# pb-autoreverse.net
KiCad netlist of a schematic drawn in Altium Designer
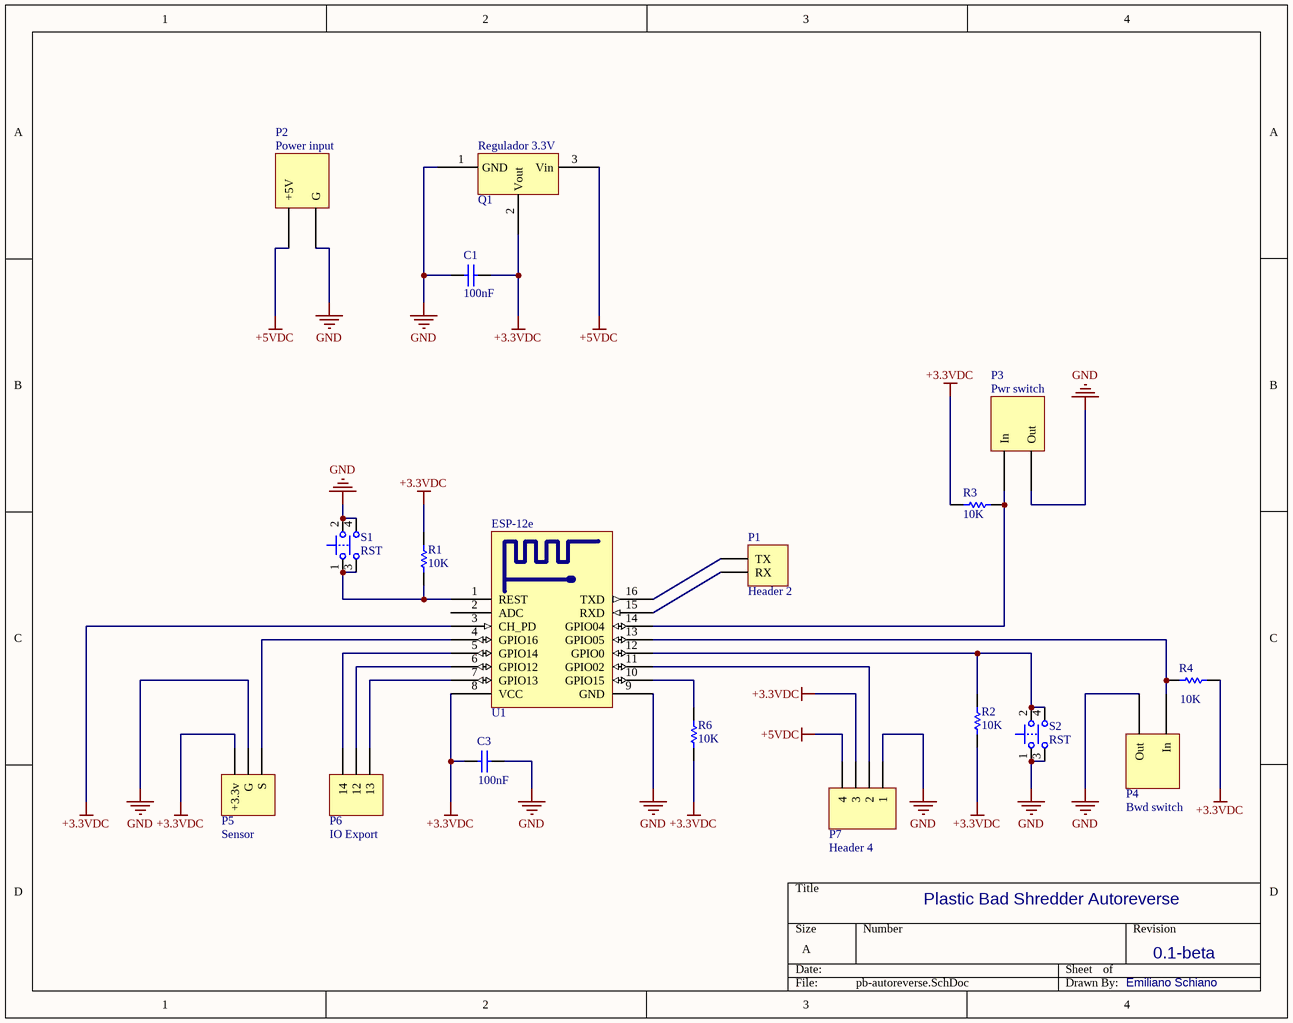
[diagram p0: pb-autoreverse.SchDoc]

(export (version "E")
  (design (tool "Eeschema 10.0.6"))
  (components
    (comp (ref "C1")
      (value "100nF")
      (footprint "RAD-0.1")
      (description "Capacitor")
      (fields (field (name "Comment") "100nf") (field (name "PUBLISHER") "Altium Limited"))
      (libsource (lib "Miscellaneous Devices") (part "Cap"))
    )
    (comp (ref "C3")
      (value "100nF")
      (footprint "RAD-0.1")
      (description "Capacitor")
      (fields (field (name "Comment") "100nf") (field (name "PUBLISHER") "Altium Limited"))
      (libsource (lib "Miscellaneous Devices") (part "Cap"))
    )
    (comp (ref "P1")
      (value "Header 2")
      (footprint "HDR1X2")
      (description "Header, 2-Pin")
      (fields (field (name "PUBLISHER") "Altium Limited"))
      (libsource (lib "Miscellaneous Connectors") (part "Header 2"))
    )
    (comp (ref "P2")
      (value "Power input")
      (footprint "ScrewTerminal-X2")
      (libsource (lib "") (part "ScrewTerminal_1"))
    )
    (comp (ref "P3")
      (value "Pwr switch")
      (footprint "ScrewTerminal-X2")
      (libsource (lib "") (part "ScrewTerminal_1"))
    )
    (comp (ref "P4")
      (value "Bwd switch")
      (footprint "ScrewTerminal-X2")
      (libsource (lib "ScrewTerminal_2X") (part "ScrewTerminal"))
    )
    (comp (ref "P5")
      (value "Sensor")
      (footprint "HDR1X3")
      (description "Header, 3-Pin")
      (fields (field (name "PUBLISHER") "Altium Limited"))
      (libsource (lib "Miscellaneous Connectors") (part "Header 3"))
    )
    (comp (ref "P6")
      (value "IO Export")
      (footprint "HDR1X3")
      (description "Header, 3-Pin")
      (fields (field (name "PUBLISHER") "Altium Limited"))
      (libsource (lib "Miscellaneous Connectors") (part "Header 3"))
    )
    (comp (ref "P7")
      (value "Header 4")
      (footprint "HDR1X4")
      (description "Header, 4-Pin")
      (fields (field (name "PUBLISHER") "Altium Limited"))
      (libsource (lib "Miscellaneous Connectors") (part "Header 4"))
    )
    (comp (ref "Q1")
      (value "Regulador 3.3V")
      (footprint "TO-220-AB")
      (libsource (lib "AMS1117") (part "AMS1117"))
    )
    (comp (ref "R1")
      (value "10K")
      (footprint "AXIAL-0.3")
      (description "Resistor")
      (fields (field (name "PUBLISHER") "Altium Limited"))
      (libsource (lib "Miscellaneous Devices") (part "Res1"))
    )
    (comp (ref "R2")
      (value "10K")
      (footprint "AXIAL-0.3")
      (description "Resistor")
      (fields (field (name "PUBLISHER") "Altium Limited"))
      (libsource (lib "Miscellaneous Devices") (part "Res1"))
    )
    (comp (ref "R3")
      (value "10K")
      (footprint "AXIAL-0.3")
      (description "Resistor")
      (fields (field (name "PUBLISHER") "Altium Limited"))
      (libsource (lib "Miscellaneous Devices") (part "Res1"))
    )
    (comp (ref "R4")
      (value "10K")
      (footprint "AXIAL-0.3")
      (description "Resistor")
      (fields (field (name "PUBLISHER") "Altium Limited"))
      (libsource (lib "Miscellaneous Devices") (part "Res1"))
    )
    (comp (ref "R6")
      (value "10K")
      (footprint "AXIAL-0.3")
      (description "Resistor")
      (fields (field (name "PUBLISHER") "Altium Limited"))
      (libsource (lib "Miscellaneous Devices") (part "Res1"))
    )
    (comp (ref "S1")
      (value "RST")
      (footprint "PushButton")
      (description "Tactile Switch, DPST; Thru-Hole; Vertical; Rating DC 12V, 50mA (max)")
      (fields (field (name "PUBLISHER") "Altium Limited"))
      (libsource (lib "IL Switch Push Button") (part "IT-2175"))
    )
    (comp (ref "S2")
      (value "RST")
      (footprint "PushButton")
      (description "Tactile Switch, DPST; Thru-Hole; Vertical; Rating DC 12V, 50mA (max)")
      (fields (field (name "PUBLISHER") "Altium Limited"))
      (libsource (lib "IL Switch Push Button") (part "IT-2175"))
    )
    (comp (ref "U1") (value "ESP-12e") (footprint "ESP_12") (libsource (lib "ESP-12") (part "ESP-12")))
  )
  (nets
    (net (code "1") (name "+3.3VDC") (class "Default")
      (node (ref "C1") (pin "2") (pinfunction "2_2") (pintype "passive"))
      (node (ref "C3") (pin "1") (pinfunction "1_1") (pintype "passive"))
      (node (ref "P5") (pin "3") (pinfunction "+3.3v_3") (pintype "passive"))
      (node (ref "P7") (pin "3") (pinfunction "3_3") (pintype "passive"))
      (node (ref "Q1") (pin "2") (pinfunction "Vout_2") (pintype "passive"))
      (node (ref "R1") (pin "1") (pinfunction "1_1") (pintype "passive"))
      (node (ref "R2") (pin "2") (pinfunction "2_2") (pintype "passive"))
      (node (ref "R3") (pin "2") (pinfunction "2_2") (pintype "passive"))
      (node (ref "R4") (pin "2") (pinfunction "2_2") (pintype "passive"))
      (node (ref "R6") (pin "1") (pinfunction "1_1") (pintype "passive"))
      (node (ref "U1") (pin "3") (pinfunction "CH_PD_3") (pintype "input"))
      (node (ref "U1") (pin "8") (pinfunction "VCC_8") (pintype "power_in"))
    )
    (net (code "2") (name "+5VDC") (class "Default")
      (node (ref "P2") (pin "1") (pinfunction "+5V_1") (pintype "passive"))
      (node (ref "P7") (pin "4") (pinfunction "4_4") (pintype "passive"))
      (node (ref "Q1") (pin "3") (pinfunction "Vin_3") (pintype "passive"))
    )
    (net (code "3") (name "GND") (class "Default")
      (node (ref "C1") (pin "1") (pinfunction "1_1") (pintype "passive"))
      (node (ref "C3") (pin "2") (pinfunction "2_2") (pintype "passive"))
      (node (ref "P2") (pin "2") (pinfunction "G_2") (pintype "passive"))
      (node (ref "P3") (pin "2") (pinfunction "G_2") (pintype "passive"))
      (node (ref "P4") (pin "2") (pinfunction "Out_2") (pintype "passive"))
      (node (ref "P5") (pin "2") (pinfunction "G_2") (pintype "passive"))
      (node (ref "P7") (pin "1") (pinfunction "1_1") (pintype "passive"))
      (node (ref "Q1") (pin "1") (pinfunction "GND_1") (pintype "passive"))
      (node (ref "S1") (pin "2") (pinfunction "2_2") (pintype "passive"))
      (node (ref "S1") (pin "4") (pinfunction "4_4") (pintype "passive"))
      (node (ref "S2") (pin "1") (pinfunction "1_1") (pintype "passive"))
      (node (ref "S2") (pin "3") (pinfunction "3_3") (pintype "passive"))
      (node (ref "U1") (pin "9") (pinfunction "GND_9") (pintype "power_in"))
    )
    (net (code "4") (name "Net-(P1-RX)") (class "Default")
      (node (ref "P1") (pin "2") (pinfunction "RX_2") (pintype "passive"))
      (node (ref "U1") (pin "15") (pinfunction "RXD_15") (pintype "input"))
    )
    (net (code "5") (name "Net-(P1-TX)") (class "Default")
      (node (ref "P1") (pin "1") (pinfunction "TX_1") (pintype "passive"))
      (node (ref "U1") (pin "16") (pinfunction "TXD_16") (pintype "output"))
    )
    (net (code "6") (name "Net-(P3-+5V)") (class "Default")
      (node (ref "P3") (pin "1") (pinfunction "+5V_1") (pintype "passive"))
      (node (ref "R3") (pin "1") (pinfunction "1_1") (pintype "passive"))
      (node (ref "U1") (pin "14") (pinfunction "GPIO04_14") (pintype "bidirectional"))
    )
    (net (code "7") (name "Net-(P4-In)") (class "Default")
      (node (ref "P4") (pin "1") (pinfunction "In_1") (pintype "passive"))
      (node (ref "R4") (pin "1") (pinfunction "1_1") (pintype "passive"))
      (node (ref "U1") (pin "13") (pinfunction "GPIO05_13") (pintype "bidirectional"))
    )
    (net (code "8") (name "Net-(P5-S)") (class "Default")
      (node (ref "P5") (pin "1") (pinfunction "S_1") (pintype "passive"))
      (node (ref "U1") (pin "4") (pinfunction "GPIO16_4") (pintype "bidirectional"))
    )
    (net (code "9") (name "Net-(P6-+3.3v)") (class "Default")
      (node (ref "P6") (pin "3") (pinfunction "+3.3v_3") (pintype "passive"))
      (node (ref "U1") (pin "5") (pinfunction "GPIO14_5") (pintype "bidirectional"))
    )
    (net (code "10") (name "Net-(P6-G)") (class "Default")
      (node (ref "P6") (pin "2") (pinfunction "G_2") (pintype "passive"))
      (node (ref "U1") (pin "6") (pinfunction "GPIO12_6") (pintype "bidirectional"))
    )
    (net (code "11") (name "Net-(P6-S)") (class "Default")
      (node (ref "P6") (pin "1") (pinfunction "S_1") (pintype "passive"))
      (node (ref "U1") (pin "7") (pinfunction "GPIO13_7") (pintype "bidirectional"))
    )
    (net (code "12") (name "Net-(U1-GPIO0)") (class "Default")
      (node (ref "R2") (pin "1") (pinfunction "1_1") (pintype "passive"))
      (node (ref "S2") (pin "2") (pinfunction "2_2") (pintype "passive"))
      (node (ref "S2") (pin "4") (pinfunction "4_4") (pintype "passive"))
      (node (ref "U1") (pin "12") (pinfunction "GPIO0_12") (pintype "bidirectional"))
    )
    (net (code "13") (name "Net-(U1-GPIO02)") (class "Default")
      (node (ref "P7") (pin "2") (pinfunction "2_2") (pintype "passive"))
      (node (ref "U1") (pin "11") (pinfunction "GPIO02_11") (pintype "bidirectional"))
    )
    (net (code "14") (name "Net-(U1-GPIO15)") (class "Default")
      (node (ref "R6") (pin "2") (pinfunction "2_2") (pintype "passive"))
      (node (ref "U1") (pin "10") (pinfunction "GPIO15_10") (pintype "bidirectional"))
    )
    (net (code "15") (name "Net-(U1-REST)") (class "Default")
      (node (ref "R1") (pin "2") (pinfunction "2_2") (pintype "passive"))
      (node (ref "S1") (pin "1") (pinfunction "1_1") (pintype "passive"))
      (node (ref "S1") (pin "3") (pinfunction "3_3") (pintype "passive"))
      (node (ref "U1") (pin "1") (pinfunction "REST_1") (pintype "passive"))
    )
    (net (code "16") (name "unconnected-(U1-ADC-Pad2)") (class "Default")
      (node (ref "U1") (pin "2") (pinfunction "ADC_2") (pintype "passive"))
    )
  )
)
